# Main_Sheet.net
KiCad netlist of a schematic drawn in Altium Designer
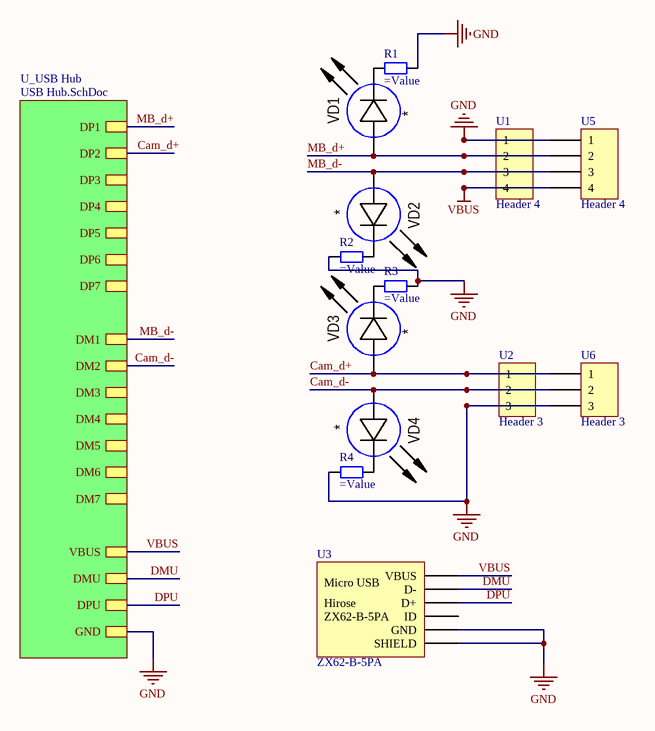
[diagram p0: Main Sheet.SchDoc]

(export (version "E")
  (design (tool "Eeschema 10.0.6"))
  (components
    (comp (ref "R1")
      (value "~")
      (footprint "res0402")
      (libsource (lib "AlexChistiakov") (part "Resistor SMD"))
    )
    (comp (ref "R2")
      (value "~")
      (footprint "res0402")
      (libsource (lib "AlexChistiakov") (part "Resistor SMD"))
    )
    (comp (ref "R3")
      (value "~")
      (footprint "res0402")
      (libsource (lib "AlexChistiakov") (part "Resistor SMD"))
    )
    (comp (ref "R4")
      (value "~")
      (footprint "res0402")
      (libsource (lib "AlexChistiakov") (part "Resistor SMD"))
    )
    (comp (ref "U1")
      (value "Header 4")
      (footprint "4x1.25")
      (libsource (lib "AlexChistiakov") (part "Header 4"))
    )
    (comp (ref "U2")
      (value "Header 3")
      (footprint "3x1.25")
      (libsource (lib "AlexChistiakov") (part "Header 3"))
    )
    (comp (ref "U3")
      (value "ZX62-B-5PA")
      (footprint "ZX62-B-5PA")
      (libsource (lib "AlexChistiakov") (part "ZX62-B-5PA"))
    )
    (comp (ref "U5")
      (value "Header 4")
      (footprint "CON: PLS-4")
      (libsource (lib "AlexChistiakov") (part "Header 4"))
    )
    (comp (ref "U6")
      (value "Header 3")
      (footprint "3x2.54")
      (libsource (lib "AlexChistiakov") (part "Header 3"))
    )
    (comp (ref "VD1") (value "*") (footprint "CH0603LB") (libsource (lib "Discrete") (part "LED")))
    (comp (ref "VD2") (value "*") (footprint "CH0603LB") (libsource (lib "Discrete") (part "LED")))
    (comp (ref "VD3") (value "*") (footprint "CH0603LB") (libsource (lib "Discrete") (part "LED")))
    (comp (ref "VD4") (value "*") (footprint "CH0603LB") (libsource (lib "Discrete") (part "LED")))
  )
  (nets
    (net (code "1") (name "/Cam_d+") (class "Default")
      (node (ref "U2") (pin "1") (pinfunction "1_1") (pintype "power_in"))
      (node (ref "U6") (pin "1") (pinfunction "1_1") (pintype "power_in"))
      (node (ref "VD3") (pin "1") (pinfunction "A_1") (pintype "passive"))
    )
    (net (code "2") (name "/Cam_d-") (class "Default")
      (node (ref "U2") (pin "2") (pinfunction "2_2") (pintype "power_in"))
      (node (ref "U6") (pin "2") (pinfunction "2_2") (pintype "power_in"))
      (node (ref "VD4") (pin "1") (pinfunction "A_1") (pintype "passive"))
    )
    (net (code "8") (name "/DMU") (class "Default")
      (node (ref "U3") (pin "2") (pinfunction "D-_2") (pintype "passive"))
    )
    (net (code "14") (name "/DPU") (class "Default")
      (node (ref "U3") (pin "3") (pinfunction "D+_3") (pintype "passive"))
    )
    (net (code "15") (name "/MB_d+") (class "Default")
      (node (ref "U1") (pin "2") (pinfunction "2_2") (pintype "power_in"))
      (node (ref "U5") (pin "2") (pinfunction "2_2") (pintype "power_in"))
      (node (ref "VD1") (pin "1") (pinfunction "A_1") (pintype "passive"))
    )
    (net (code "16") (name "/MB_d-") (class "Default")
      (node (ref "U1") (pin "3") (pinfunction "3_3") (pintype "power_in"))
      (node (ref "U5") (pin "3") (pinfunction "3_3") (pintype "power_in"))
      (node (ref "VD2") (pin "1") (pinfunction "A_1") (pintype "passive"))
    )
    (net (code "17") (name "GND") (class "Default")
      (node (ref "R1") (pin "2") (pinfunction "2_2") (pintype "passive"))
      (node (ref "R2") (pin "1") (pinfunction "1_1") (pintype "passive"))
      (node (ref "R3") (pin "2") (pinfunction "2_2") (pintype "passive"))
      (node (ref "R4") (pin "1") (pinfunction "1_1") (pintype "passive"))
      (node (ref "U1") (pin "1") (pinfunction "1_1") (pintype "power_in"))
      (node (ref "U2") (pin "3") (pinfunction "3_3") (pintype "power_in"))
      (node (ref "U3") (pin "5") (pinfunction "GND_5") (pintype "passive"))
      (node (ref "U3") (pin "6") (pinfunction "SHIELD_6") (pintype "passive"))
      (node (ref "U5") (pin "1") (pinfunction "1_1") (pintype "power_in"))
      (node (ref "U6") (pin "3") (pinfunction "3_3") (pintype "power_in"))
    )
    (net (code "18") (name "Net-(VD1-C)") (class "Default")
      (node (ref "R1") (pin "1") (pinfunction "1_1") (pintype "passive"))
      (node (ref "VD1") (pin "2") (pinfunction "C_2") (pintype "passive"))
    )
    (net (code "19") (name "Net-(VD2-C)") (class "Default")
      (node (ref "R2") (pin "2") (pinfunction "2_2") (pintype "passive"))
      (node (ref "VD2") (pin "2") (pinfunction "C_2") (pintype "passive"))
    )
    (net (code "20") (name "Net-(VD3-C)") (class "Default")
      (node (ref "R3") (pin "1") (pinfunction "1_1") (pintype "passive"))
      (node (ref "VD3") (pin "2") (pinfunction "C_2") (pintype "passive"))
    )
    (net (code "21") (name "Net-(VD4-C)") (class "Default")
      (node (ref "R4") (pin "2") (pinfunction "2_2") (pintype "passive"))
      (node (ref "VD4") (pin "2") (pinfunction "C_2") (pintype "passive"))
    )
    (net (code "22") (name "VBUS") (class "Default")
      (node (ref "U1") (pin "4") (pinfunction "4_4") (pintype "power_in"))
      (node (ref "U3") (pin "1") (pinfunction "VBUS_1") (pintype "passive"))
      (node (ref "U5") (pin "4") (pinfunction "4_4") (pintype "power_in"))
    )
    (net (code "23") (name "unconnected-(U3-ID-Pad4)") (class "Default")
      (node (ref "U3") (pin "4") (pinfunction "ID_4") (pintype "passive"))
    )
  )
)
